# TERMOCOUPLER-1.net
KiCad netlist of a schematic drawn in EAGLE
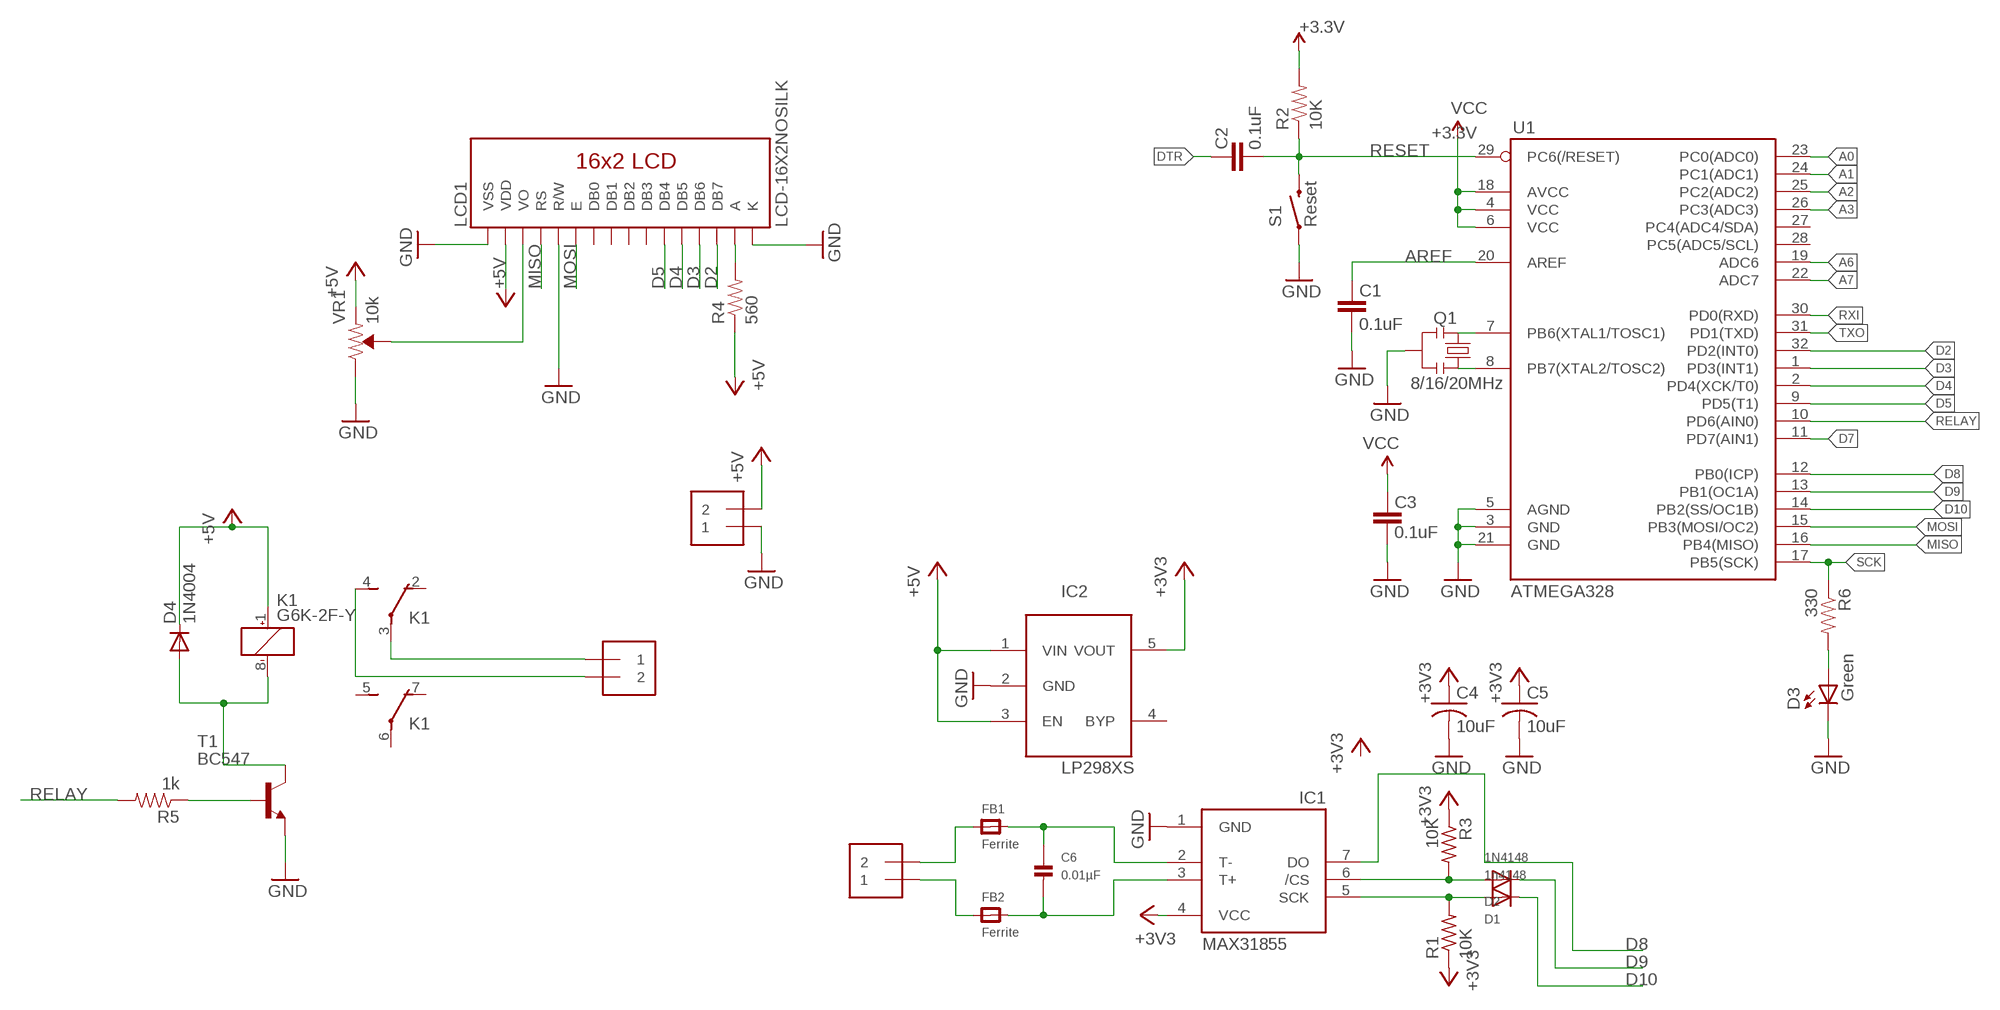
[diagram p0: schematic, sheet 1]

(export (version "E")
  (design (tool "Eeschema 10.0.6"))
  (components
    (comp (ref "C1")
      (value "0.1uF")
      (footprint "eagle-import:0603-CAP")
      (libsource (lib "eagle-import") (part "CAP0603-CAP"))
    )
    (comp (ref "C2")
      (value "0.1uF")
      (footprint "eagle-import:0603-CAP")
      (libsource (lib "eagle-import") (part "CAP0603-CAP"))
    )
    (comp (ref "C3")
      (value "0.1uF")
      (footprint "eagle-import:0603-CAP")
      (libsource (lib "eagle-import") (part "CAP0603-CAP"))
    )
    (comp (ref "C4")
      (value "10uF")
      (footprint "eagle-import:C0805K")
      (libsource (lib "eagle-import") (part "C-USC0805K"))
    )
    (comp (ref "C5")
      (value "10uF")
      (footprint "eagle-import:C0805K")
      (libsource (lib "eagle-import") (part "C-USC0805K"))
    )
    (comp (ref "C6")
      (value "0.01µF")
      (footprint "eagle-import:_0805")
      (libsource (lib "eagle-import") (part "CAP_CERAMIC_0805"))
    )
    (comp (ref "D1")
      (value "1n4148")
      (footprint "eagle-import:SOD-323F")
      (libsource (lib "eagle-import") (part "DIODESOD-323F"))
    )
    (comp (ref "D2")
      (value "1N4148")
      (footprint "eagle-import:SOD-323F")
      (libsource (lib "eagle-import") (part "DIODESOD-323F"))
    )
    (comp (ref "D3")
      (value "Green")
      (footprint "eagle-import:0603-LED-ALT1")
      (libsource (lib "eagle-import") (part "LED"))
    )
    (comp (ref "D4")
      (value "1N4004")
      (footprint "eagle-import:DO41-10")
      (libsource (lib "eagle-import") (part "1N4004"))
    )
    (comp (ref "FB1")
      (value "Ferrite")
      (footprint "eagle-import:_0805")
      (libsource (lib "eagle-import") (part "FERRITE_0805"))
    )
    (comp (ref "FB2")
      (value "Ferrite")
      (footprint "eagle-import:_0805")
      (libsource (lib "eagle-import") (part "FERRITE_0805"))
    )
    (comp (ref "IC1")
      (value "MAX31855")
      (footprint "eagle-import:SO08")
      (libsource (lib "eagle-import") (part "MAX6675"))
    )
    (comp (ref "IC2")
      (value "LP298XS")
      (footprint "eagle-import:SOT23-5L")
      (libsource (lib "eagle-import") (part "LP298XS"))
    )
    (comp (ref "J1")
      (value "1X2-3.5MM")
      (footprint "eagle-import:1X2-3.5MM")
      (libsource (lib "eagle-import") (part "1X2-3.5MM"))
    )
    (comp (ref "J2")
      (value "1X2-3.5MM")
      (footprint "eagle-import:1X2-3.5MM")
      (libsource (lib "eagle-import") (part "1X2-3.5MM"))
    )
    (comp (ref "J3")
      (value "1X2-3.5MM")
      (footprint "eagle-import:1X2-3.5MM")
      (libsource (lib "eagle-import") (part "1X2-3.5MM"))
    )
    (comp (ref "K1")
      (value "G6K-2F-Y")
      (footprint "eagle-import:G6K-2F-Y")
      (fields (field (name "MF") "OMRON COMPONENTS USA") (field (name "MPN") "G6K-2F-Y DC3"))
      (libsource (lib "eagle-import") (part "G6K-2F-Y"))
    )
    (comp (ref "LCD1")
      (value "LCD-16X2NOSILK")
      (footprint "eagle-import:LCD-16X2_NOSILK")
      (libsource (lib "eagle-import") (part "LCD-16X2NOSILK"))
    )
    (comp (ref "Q1")
      (value "8/16/20MHz")
      (footprint "eagle-import:RESONATOR-SMD-1_1")
      (libsource (lib "eagle-import") (part "RESONATOR1{colon}1"))
    )
    (comp (ref "R1")
      (value "10K")
      (footprint "eagle-import:R0805")
      (libsource (lib "eagle-import") (part "R-US_R0805"))
    )
    (comp (ref "R2")
      (value "10K")
      (footprint "eagle-import:0603-RES")
      (libsource (lib "eagle-import") (part "RESISTOR0603-RES"))
    )
    (comp (ref "R3")
      (value "10K")
      (footprint "eagle-import:R0805")
      (libsource (lib "eagle-import") (part "R-US_R0805"))
    )
    (comp (ref "R4")
      (value "560")
      (footprint "eagle-import:0603-RES")
      (libsource (lib "eagle-import") (part "RESISTOR0603-RES"))
    )
    (comp (ref "R5")
      (value "1k")
      (footprint "eagle-import:0603-RES")
      (libsource (lib "eagle-import") (part "RESISTOR0603-RES"))
    )
    (comp (ref "R6")
      (value "330")
      (footprint "eagle-import:0603-RES")
      (libsource (lib "eagle-import") (part "RESISTOR0603-RES"))
    )
    (comp (ref "S1")
      (value "Reset")
      (footprint "eagle-import:TACTILE-SWITCH-SMD-ALT01")
      (libsource (lib "eagle-import") (part "SWITCH-MOMENTARY-2SMD-ALT01"))
    )
    (comp (ref "T1")
      (value "BC547")
      (footprint "eagle-import:TO92")
      (libsource (lib "eagle-import") (part "BC547"))
    )
    (comp (ref "U1")
      (value "ATMEGA328")
      (footprint "eagle-import:TQFP32-08")
      (libsource (lib "eagle-import") (part "ATMEGA168"))
    )
    (comp (ref "VR1")
      (value "10k")
      (footprint "eagle-import:TRIMPOT-SMD-3MM-CLOSED")
      (libsource (lib "eagle-import") (part "TRIMPOT-SMD-3MM-CLOSED-1/8W-20%"))
    )
  )
  (nets
    (net (code "1") (name "+3V3") (class "Default")
      (node (ref "C4") (pin "1") (pinfunction "1_1") (pintype "passive"))
      (node (ref "C5") (pin "1") (pinfunction "1_1") (pintype "passive"))
      (node (ref "IC1") (pin "4") (pinfunction "VCC_4") (pintype "power_in"))
      (node (ref "IC2") (pin "5") (pinfunction "VOUT_5") (pintype "bidirectional"))
      (node (ref "R1") (pin "1") (pinfunction "1_1") (pintype "passive"))
      (node (ref "R3") (pin "1") (pinfunction "1_1") (pintype "passive"))
    )
    (net (code "2") (name "+5V") (class "Default")
      (node (ref "D4") (pin "C") (pinfunction "C_C") (pintype "passive"))
      (node (ref "IC2") (pin "1") (pinfunction "VIN_1") (pintype "bidirectional"))
      (node (ref "IC2") (pin "3") (pinfunction "EN_3") (pintype "bidirectional"))
      (node (ref "J2") (pin "2") (pinfunction "2_2") (pintype "passive"))
      (node (ref "K1") (pin "1") (pinfunction "+_1") (pintype "passive"))
      (node (ref "LCD1") (pin "2") (pinfunction "VDD_2") (pintype "power_in"))
      (node (ref "R4") (pin "1") (pinfunction "1_1") (pintype "passive"))
      (node (ref "VR1") (pin "1") (pinfunction "CCW_1") (pintype "passive"))
    )
    (net (code "3") (name "/AREF") (class "Default")
      (node (ref "C1") (pin "2") (pinfunction "2_2") (pintype "passive"))
      (node (ref "U1") (pin "20") (pinfunction "AREF_20") (pintype "bidirectional"))
    )
    (net (code "4") (name "/RESET") (class "Default")
      (node (ref "C2") (pin "1") (pinfunction "1_1") (pintype "passive"))
      (node (ref "R2") (pin "1") (pinfunction "1_1") (pintype "passive"))
      (node (ref "S1") (pin "3") (pinfunction "2_3") (pintype "passive"))
      (node (ref "S1") (pin "4") (pinfunction "2_4") (pintype "passive"))
      (node (ref "U1") (pin "29") (pinfunction "PC6(/RESET)_29") (pintype "bidirectional"))
    )
    (net (code "5") (name "A0") (class "Default")
      (node (ref "U1") (pin "23") (pinfunction "PC0(ADC0)_23") (pintype "bidirectional"))
    )
    (net (code "6") (name "A1") (class "Default")
      (node (ref "U1") (pin "24") (pinfunction "PC1(ADC1)_24") (pintype "bidirectional"))
    )
    (net (code "7") (name "A2") (class "Default")
      (node (ref "U1") (pin "25") (pinfunction "PC2(ADC2)_25") (pintype "bidirectional"))
    )
    (net (code "8") (name "A3") (class "Default")
      (node (ref "U1") (pin "26") (pinfunction "PC3(ADC3)_26") (pintype "bidirectional"))
    )
    (net (code "9") (name "A6") (class "Default")
      (node (ref "U1") (pin "19") (pinfunction "ADC6_19") (pintype "bidirectional"))
    )
    (net (code "10") (name "A7") (class "Default")
      (node (ref "U1") (pin "22") (pinfunction "ADC7_22") (pintype "bidirectional"))
    )
    (net (code "11") (name "D2") (class "Default")
      (node (ref "LCD1") (pin "14") (pinfunction "DB7_14") (pintype "bidirectional"))
      (node (ref "U1") (pin "32") (pinfunction "PD2(INT0)_32") (pintype "bidirectional"))
    )
    (net (code "12") (name "D3") (class "Default")
      (node (ref "LCD1") (pin "13") (pinfunction "DB6_13") (pintype "bidirectional"))
      (node (ref "U1") (pin "1") (pinfunction "PD3(INT1)_1") (pintype "bidirectional"))
    )
    (net (code "13") (name "D4") (class "Default")
      (node (ref "LCD1") (pin "12") (pinfunction "DB5_12") (pintype "bidirectional"))
      (node (ref "U1") (pin "2") (pinfunction "PD4(XCK/T0)_2") (pintype "bidirectional"))
    )
    (net (code "14") (name "D5") (class "Default")
      (node (ref "LCD1") (pin "11") (pinfunction "DB4_11") (pintype "bidirectional"))
      (node (ref "U1") (pin "9") (pinfunction "PD5(T1)_9") (pintype "bidirectional"))
    )
    (net (code "15") (name "D7") (class "Default")
      (node (ref "U1") (pin "11") (pinfunction "PD7(AIN1)_11") (pintype "bidirectional"))
    )
    (net (code "16") (name "D8") (class "Default")
      (node (ref "IC1") (pin "7") (pinfunction "DO_7") (pintype "output"))
      (node (ref "U1") (pin "12") (pinfunction "PB0(ICP)_12") (pintype "bidirectional"))
    )
    (net (code "17") (name "D9") (class "Default")
      (node (ref "D2") (pin "C") (pinfunction "C_C") (pintype "passive"))
      (node (ref "U1") (pin "13") (pinfunction "PB1(OC1A)_13") (pintype "bidirectional"))
    )
    (net (code "18") (name "D10") (class "Default")
      (node (ref "D1") (pin "C") (pinfunction "C_C") (pintype "passive"))
      (node (ref "U1") (pin "14") (pinfunction "PB2(SS/OC1B)_14") (pintype "bidirectional"))
    )
    (net (code "19") (name "DTR") (class "Default")
      (node (ref "C2") (pin "2") (pinfunction "2_2") (pintype "passive"))
    )
    (net (code "20") (name "GND") (class "Default")
      (node (ref "C1") (pin "1") (pinfunction "1_1") (pintype "passive"))
      (node (ref "C3") (pin "1") (pinfunction "1_1") (pintype "passive"))
      (node (ref "C4") (pin "2") (pinfunction "2_2") (pintype "passive"))
      (node (ref "C5") (pin "2") (pinfunction "2_2") (pintype "passive"))
      (node (ref "D3") (pin "C") (pinfunction "C_C") (pintype "passive"))
      (node (ref "IC1") (pin "1") (pinfunction "GND_1") (pintype "power_in"))
      (node (ref "IC2") (pin "2") (pinfunction "GND_2") (pintype "bidirectional"))
      (node (ref "J2") (pin "1") (pinfunction "1_1") (pintype "passive"))
      (node (ref "LCD1") (pin "1") (pinfunction "VSS_1") (pintype "power_in"))
      (node (ref "LCD1") (pin "16") (pinfunction "K_16") (pintype "power_in"))
      (node (ref "LCD1") (pin "5") (pinfunction "R/W_5") (pintype "input"))
      (node (ref "Q1") (pin "2") (pinfunction "2_2") (pintype "passive"))
      (node (ref "S1") (pin "1") (pinfunction "1_1") (pintype "passive"))
      (node (ref "S1") (pin "2") (pinfunction "1_2") (pintype "passive"))
      (node (ref "T1") (pin "1") (pinfunction "E_1") (pintype "passive"))
      (node (ref "U1") (pin "21") (pinfunction "GND_21") (pintype "bidirectional"))
      (node (ref "U1") (pin "3") (pinfunction "GND_3") (pintype "bidirectional"))
      (node (ref "U1") (pin "5") (pinfunction "AGND_5") (pintype "bidirectional"))
      (node (ref "VR1") (pin "3") (pinfunction "CW_3") (pintype "passive"))
    )
    (net (code "21") (name "MISO") (class "Default")
      (node (ref "LCD1") (pin "4") (pinfunction "RS_4") (pintype "input"))
      (node (ref "U1") (pin "16") (pinfunction "PB4(MISO)_16") (pintype "bidirectional"))
    )
    (net (code "22") (name "MOSI") (class "Default")
      (node (ref "LCD1") (pin "6") (pinfunction "E_6") (pintype "input"))
      (node (ref "U1") (pin "15") (pinfunction "PB3(MOSI/OC2)_15") (pintype "bidirectional"))
    )
    (net (code "23") (name "Net-(C6-P$1)") (class "Default")
      (node (ref "C6") (pin "1") (pinfunction "P$1_1") (pintype "passive"))
      (node (ref "FB1") (pin "2") (pinfunction "P$2_2") (pintype "passive"))
      (node (ref "IC1") (pin "2") (pinfunction "T-_2") (pintype "input"))
    )
    (net (code "24") (name "Net-(C6-P$2)") (class "Default")
      (node (ref "C6") (pin "2") (pinfunction "P$2_2") (pintype "passive"))
      (node (ref "FB2") (pin "2") (pinfunction "P$2_2") (pintype "passive"))
      (node (ref "IC1") (pin "3") (pinfunction "T+_3") (pintype "input"))
    )
    (net (code "25") (name "Net-(D3-PadA)") (class "Default")
      (node (ref "D3") (pin "A") (pinfunction "A_A") (pintype "passive"))
      (node (ref "R6") (pin "2") (pinfunction "2_2") (pintype "passive"))
    )
    (net (code "26") (name "Net-(FB1-P$1)") (class "Default")
      (node (ref "FB1") (pin "1") (pinfunction "P$1_1") (pintype "passive"))
      (node (ref "J1") (pin "2") (pinfunction "2_2") (pintype "passive"))
    )
    (net (code "27") (name "Net-(FB2-P$1)") (class "Default")
      (node (ref "FB2") (pin "1") (pinfunction "P$1_1") (pintype "passive"))
      (node (ref "J1") (pin "1") (pinfunction "1_1") (pintype "passive"))
    )
    (net (code "28") (name "Net-(IC1-SCK)") (class "Default")
      (node (ref "D1") (pin "A") (pinfunction "A_A") (pintype "passive"))
      (node (ref "IC1") (pin "5") (pinfunction "SCK_5") (pintype "input"))
      (node (ref "R1") (pin "2") (pinfunction "2_2") (pintype "passive"))
    )
    (net (code "29") (name "Net-(IC1-{slash}CS)") (class "Default")
      (node (ref "D2") (pin "A") (pinfunction "A_A") (pintype "passive"))
      (node (ref "IC1") (pin "6") (pinfunction "/CS_6") (pintype "input"))
      (node (ref "R3") (pin "2") (pinfunction "2_2") (pintype "passive"))
    )
    (net (code "30") (name "Net-(K1A--)") (class "Default")
      (node (ref "D4") (pin "A") (pinfunction "A_A") (pintype "passive"))
      (node (ref "K1") (pin "8") (pinfunction "-_8") (pintype "passive"))
      (node (ref "T1") (pin "3") (pinfunction "C_3") (pintype "passive"))
    )
    (net (code "31") (name "Net-(K1B-P)") (class "Default")
      (node (ref "J3") (pin "1") (pinfunction "1_1") (pintype "passive"))
      (node (ref "K1") (pin "3") (pinfunction "P_3") (pintype "passive"))
    )
    (net (code "32") (name "Net-(K1B-S)") (class "Default")
      (node (ref "J3") (pin "2") (pinfunction "2_2") (pintype "passive"))
      (node (ref "K1") (pin "4") (pinfunction "S_4") (pintype "passive"))
    )
    (net (code "33") (name "Net-(LCD1-A)") (class "Default")
      (node (ref "LCD1") (pin "15") (pinfunction "A_15") (pintype "power_in"))
      (node (ref "R4") (pin "2") (pinfunction "2_2") (pintype "passive"))
    )
    (net (code "34") (name "Net-(LCD1-VO)") (class "Default")
      (node (ref "LCD1") (pin "3") (pinfunction "VO_3") (pintype "bidirectional"))
      (node (ref "VR1") (pin "2") (pinfunction "WIPER_2") (pintype "passive"))
    )
    (net (code "35") (name "Net-(T1-B)") (class "Default")
      (node (ref "R5") (pin "1") (pinfunction "1_1") (pintype "passive"))
      (node (ref "T1") (pin "2") (pinfunction "B_2") (pintype "passive"))
    )
    (net (code "36") (name "Net-(U1-PB6(XTAL1{slash}TOSC1))") (class "Default")
      (node (ref "Q1") (pin "1") (pinfunction "1_1") (pintype "passive"))
      (node (ref "U1") (pin "7") (pinfunction "PB6(XTAL1/TOSC1)_7") (pintype "bidirectional"))
    )
    (net (code "37") (name "Net-(U1-PB7(XTAL2{slash}TOSC2))") (class "Default")
      (node (ref "Q1") (pin "3") (pinfunction "3_3") (pintype "passive"))
      (node (ref "U1") (pin "8") (pinfunction "PB7(XTAL2/TOSC2)_8") (pintype "bidirectional"))
    )
    (net (code "38") (name "RELAY") (class "Default")
      (node (ref "R5") (pin "2") (pinfunction "2_2") (pintype "passive"))
      (node (ref "U1") (pin "10") (pinfunction "PD6(AIN0)_10") (pintype "bidirectional"))
    )
    (net (code "39") (name "RXI") (class "Default")
      (node (ref "U1") (pin "30") (pinfunction "PD0(RXD)_30") (pintype "bidirectional"))
    )
    (net (code "40") (name "SCK") (class "Default")
      (node (ref "R6") (pin "1") (pinfunction "1_1") (pintype "passive"))
      (node (ref "U1") (pin "17") (pinfunction "PB5(SCK)_17") (pintype "bidirectional"))
    )
    (net (code "41") (name "TXO") (class "Default")
      (node (ref "U1") (pin "31") (pinfunction "PD1(TXD)_31") (pintype "bidirectional"))
    )
    (net (code "42") (name "VCC") (class "Default")
      (node (ref "C3") (pin "2") (pinfunction "2_2") (pintype "passive"))
      (node (ref "R2") (pin "2") (pinfunction "2_2") (pintype "passive"))
      (node (ref "U1") (pin "18") (pinfunction "AVCC_18") (pintype "bidirectional"))
      (node (ref "U1") (pin "4") (pinfunction "VCC_4") (pintype "bidirectional"))
      (node (ref "U1") (pin "6") (pinfunction "VCC_6") (pintype "bidirectional"))
    )
    (net (code "43") (name "unconnected-(IC2-BYP-Pad4)") (class "Default")
      (node (ref "IC2") (pin "4") (pinfunction "BYP_4") (pintype "bidirectional"))
    )
    (net (code "44") (name "unconnected-(K1B-O-Pad2)") (class "Default")
      (node (ref "K1") (pin "2") (pinfunction "O_2") (pintype "passive"))
    )
    (net (code "45") (name "unconnected-(K1C-O-Pad7)") (class "Default")
      (node (ref "K1") (pin "7") (pinfunction "O_7") (pintype "passive"))
    )
    (net (code "46") (name "unconnected-(K1C-P-Pad6)") (class "Default")
      (node (ref "K1") (pin "6") (pinfunction "P_6") (pintype "passive"))
    )
    (net (code "47") (name "unconnected-(K1C-S-Pad5)") (class "Default")
      (node (ref "K1") (pin "5") (pinfunction "S_5") (pintype "passive"))
    )
    (net (code "48") (name "unconnected-(LCD1-DB0-Pad7)") (class "Default")
      (node (ref "LCD1") (pin "7") (pinfunction "DB0_7") (pintype "bidirectional"))
    )
    (net (code "49") (name "unconnected-(LCD1-DB1-Pad8)") (class "Default")
      (node (ref "LCD1") (pin "8") (pinfunction "DB1_8") (pintype "bidirectional"))
    )
    (net (code "50") (name "unconnected-(LCD1-DB2-Pad9)") (class "Default")
      (node (ref "LCD1") (pin "9") (pinfunction "DB2_9") (pintype "bidirectional"))
    )
    (net (code "51") (name "unconnected-(LCD1-DB3-Pad10)") (class "Default")
      (node (ref "LCD1") (pin "10") (pinfunction "DB3_10") (pintype "bidirectional"))
    )
    (net (code "52") (name "unconnected-(U1-PC4(ADC4{slash}SDA)-Pad27)") (class "Default")
      (node (ref "U1") (pin "27") (pinfunction "PC4(ADC4/SDA)_27") (pintype "bidirectional"))
    )
    (net (code "53") (name "unconnected-(U1-PC5(ADC5{slash}SCL)-Pad28)") (class "Default")
      (node (ref "U1") (pin "28") (pinfunction "PC5(ADC5/SCL)_28") (pintype "bidirectional"))
    )
  )
)
